# design.net
KiCad netlist of a schematic drawn in EasyEDA Pro
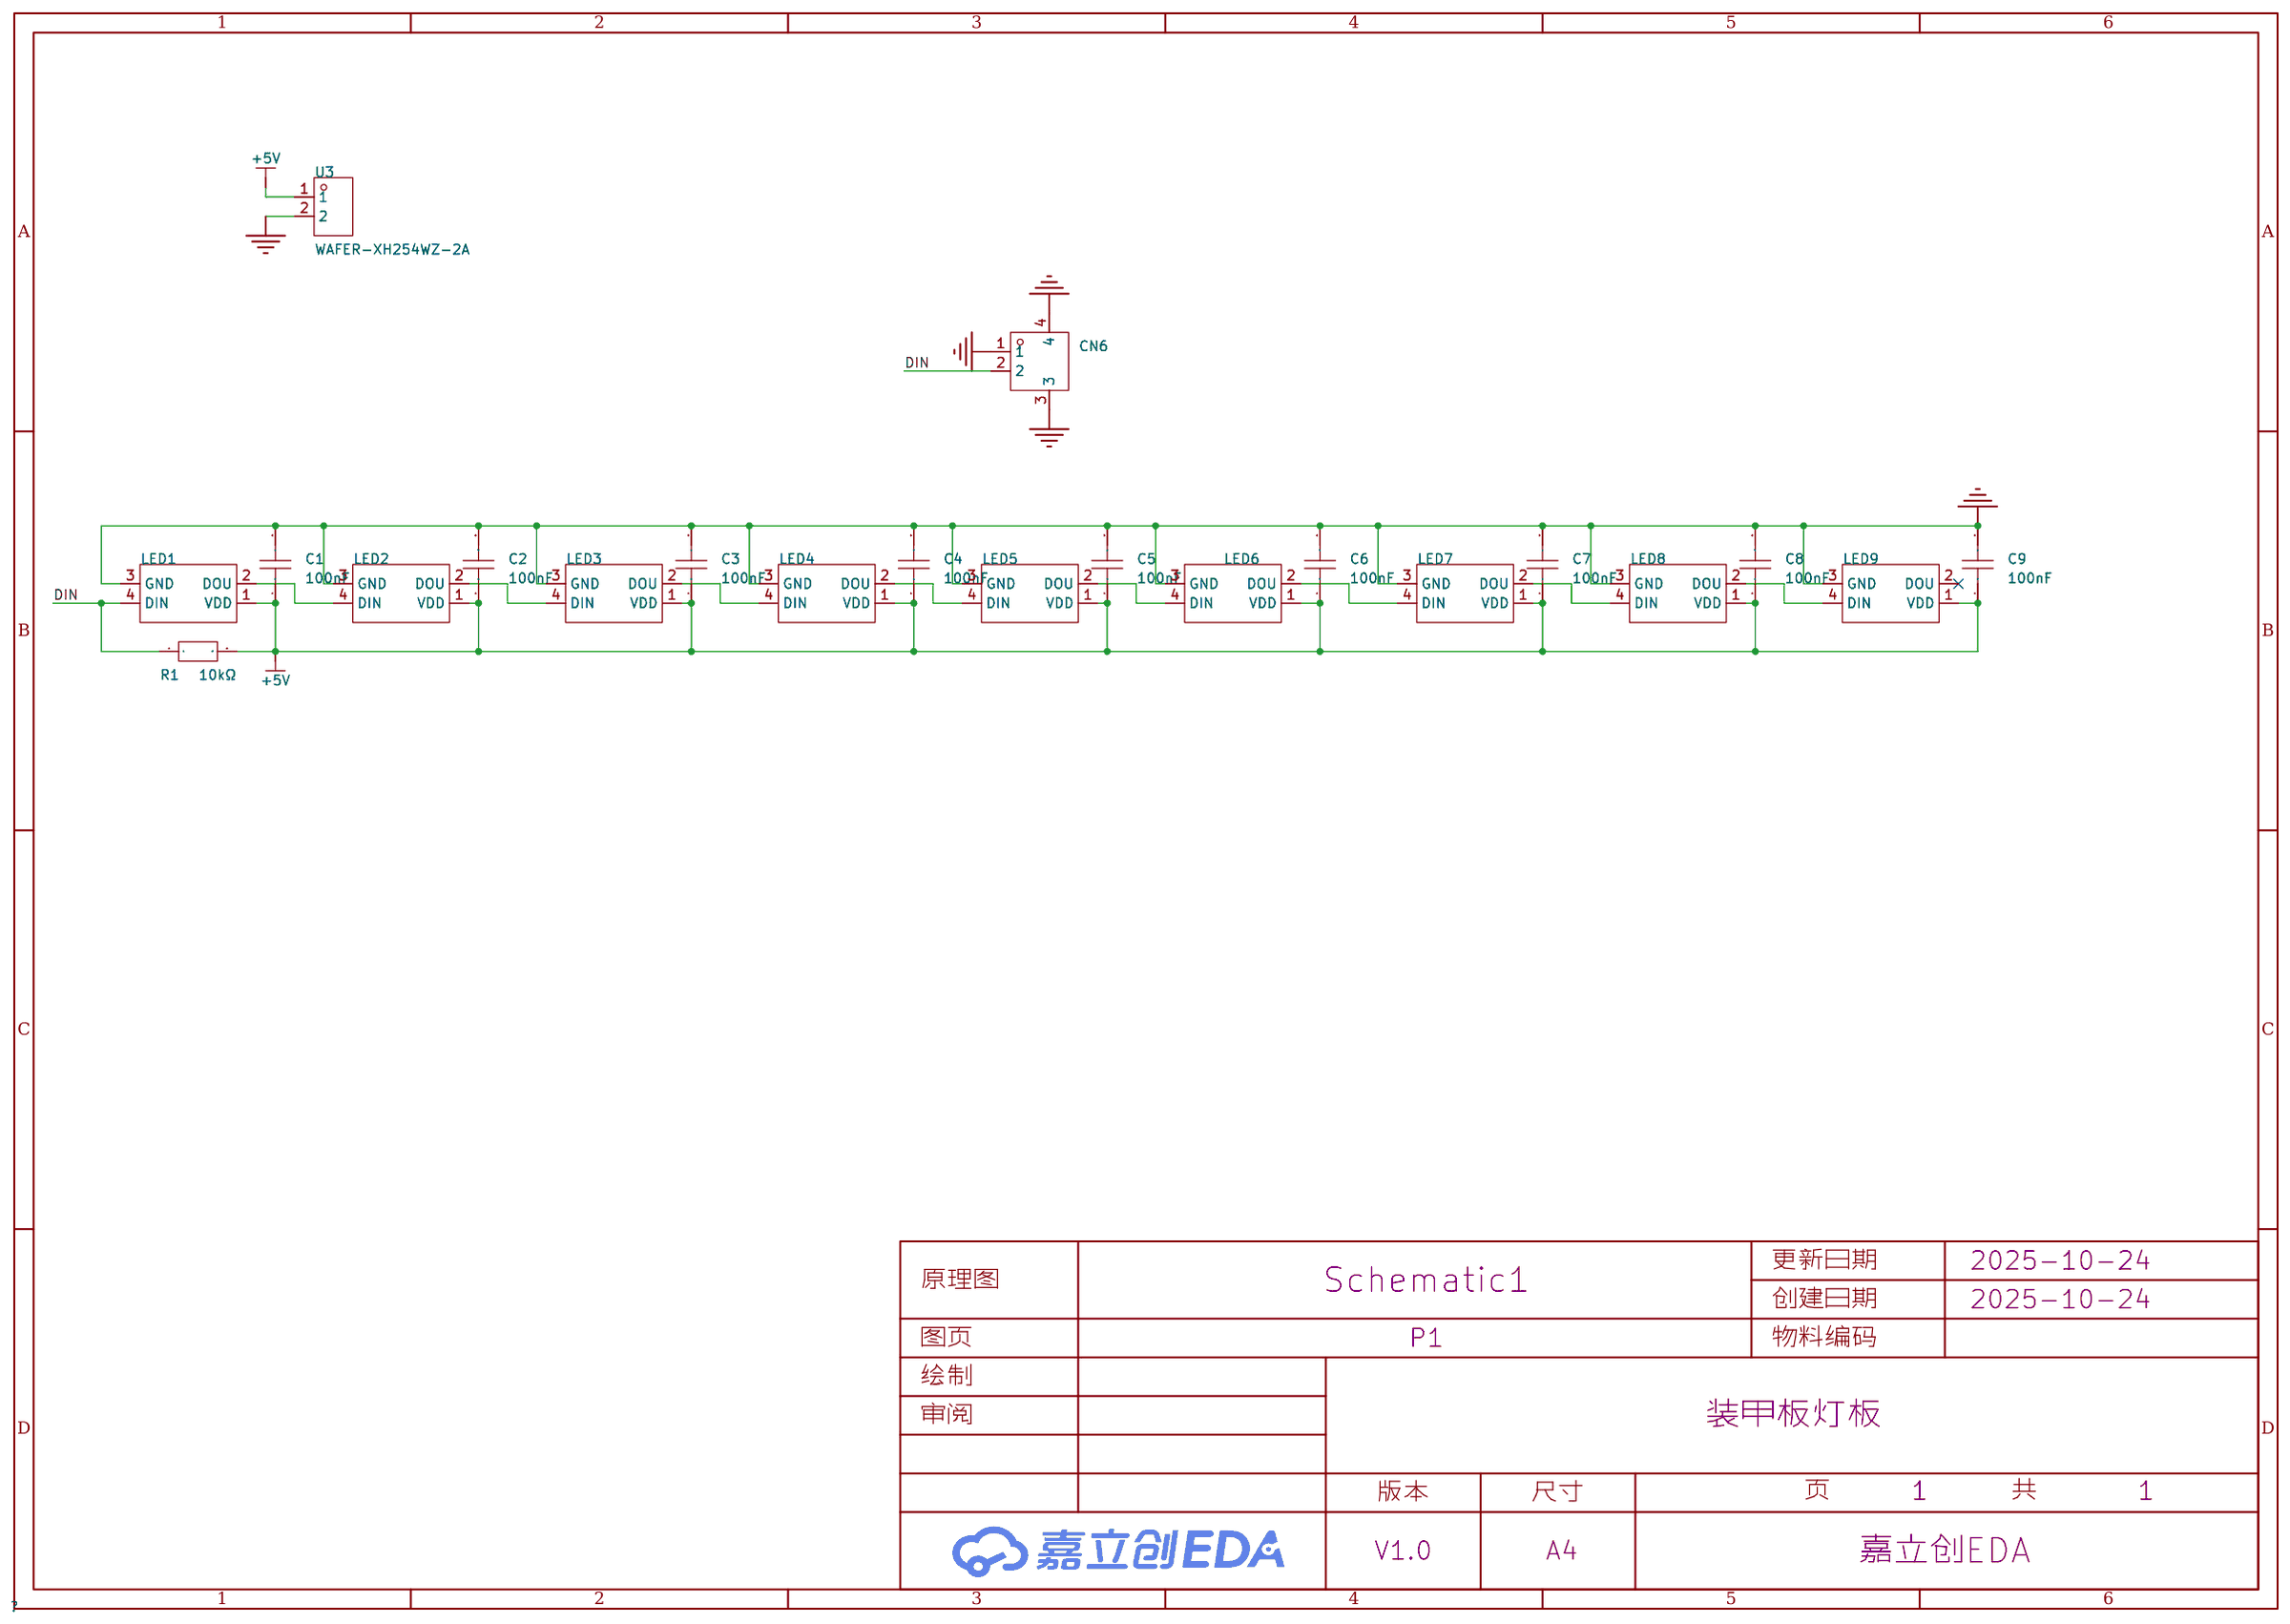
[diagram p0: schematic sheet]

(export (version "E")
  (design (tool "Eeschema 10.0.6"))
  (components
    (comp (ref "C1")
      (value "100nF")
      (footprint "easyedapro:C0603")
      (description "容值:100nF;精度:±20%;额定电压:50V;")
      (fields
        (field (name "Manufacturer Part") "NL0603B104M500CPBN")
        (field (name "Manufacturer") "HUI JU(汇聚)")
      )
      (libsource (lib "easyedapro") (part "NL0603B104M500CPBN"))
    )
    (comp (ref "C2")
      (value "100nF")
      (footprint "easyedapro:C0603")
      (description "容值:100nF;精度:±20%;额定电压:50V;")
      (fields
        (field (name "Manufacturer Part") "NL0603B104M500CPBN")
        (field (name "Manufacturer") "HUI JU(汇聚)")
      )
      (libsource (lib "easyedapro") (part "NL0603B104M500CPBN"))
    )
    (comp (ref "C3")
      (value "100nF")
      (footprint "easyedapro:C0603")
      (description "容值:100nF;精度:±20%;额定电压:50V;")
      (fields
        (field (name "Manufacturer Part") "NL0603B104M500CPBN")
        (field (name "Manufacturer") "HUI JU(汇聚)")
      )
      (libsource (lib "easyedapro") (part "NL0603B104M500CPBN"))
    )
    (comp (ref "C4")
      (value "100nF")
      (footprint "easyedapro:C0603")
      (description "容值:100nF;精度:±20%;额定电压:50V;")
      (fields
        (field (name "Manufacturer Part") "NL0603B104M500CPBN")
        (field (name "Manufacturer") "HUI JU(汇聚)")
      )
      (libsource (lib "easyedapro") (part "NL0603B104M500CPBN"))
    )
    (comp (ref "C5")
      (value "100nF")
      (footprint "easyedapro:C0603")
      (description "容值:100nF;精度:±20%;额定电压:50V;")
      (fields
        (field (name "Manufacturer Part") "NL0603B104M500CPBN")
        (field (name "Manufacturer") "HUI JU(汇聚)")
      )
      (libsource (lib "easyedapro") (part "NL0603B104M500CPBN"))
    )
    (comp (ref "C6")
      (value "100nF")
      (footprint "easyedapro:C0603")
      (description "容值:100nF;精度:±20%;额定电压:50V;")
      (fields
        (field (name "Manufacturer Part") "NL0603B104M500CPBN")
        (field (name "Manufacturer") "HUI JU(汇聚)")
      )
      (libsource (lib "easyedapro") (part "NL0603B104M500CPBN"))
    )
    (comp (ref "C7")
      (value "100nF")
      (footprint "easyedapro:C0603")
      (description "容值:100nF;精度:±20%;额定电压:50V;")
      (fields
        (field (name "Manufacturer Part") "NL0603B104M500CPBN")
        (field (name "Manufacturer") "HUI JU(汇聚)")
      )
      (libsource (lib "easyedapro") (part "NL0603B104M500CPBN"))
    )
    (comp (ref "C8")
      (value "100nF")
      (footprint "easyedapro:C0603")
      (description "容值:100nF;精度:±20%;额定电压:50V;")
      (fields
        (field (name "Manufacturer Part") "NL0603B104M500CPBN")
        (field (name "Manufacturer") "HUI JU(汇聚)")
      )
      (libsource (lib "easyedapro") (part "NL0603B104M500CPBN"))
    )
    (comp (ref "C9")
      (value "100nF")
      (footprint "easyedapro:C0603")
      (description "容值:100nF;精度:±20%;额定电压:50V;")
      (fields
        (field (name "Manufacturer Part") "NL0603B104M500CPBN")
        (field (name "Manufacturer") "HUI JU(汇聚)")
      )
      (libsource (lib "easyedapro") (part "NL0603B104M500CPBN"))
    )
    (comp (ref "CN6")
      (value "X1251WVS-02HF-LPSW")
      (footprint "easyedapro:郭哥CAN2脚母接口")
      (fields (field (name "Manufacturer") "XKB Enterprise"))
      (libsource (lib "easyedapro") (part "X1251WVS-02HF-LPSW"))
    )
    (comp (ref "LED1")
      (value "XL-5050RGBC-2812B")
      (footprint "easyedapro:LED-SMD_4P-L5.0-W5.0-BL_XL-5050RGBC")
      (description "5050幻彩透明  内置驱动  IC WS2812B")
      (fields (field (name "Manufacturer") "XINGLIGHT(成兴光)"))
      (libsource (lib "easyedapro") (part "XL-5050RGBC-WS2812B"))
    )
    (comp (ref "LED2")
      (value "XL-5050RGBC-2812B")
      (footprint "easyedapro:LED-SMD_4P-L5.0-W5.0-BL_XL-5050RGBC")
      (description "5050幻彩透明  内置驱动  IC WS2812B")
      (fields (field (name "Manufacturer") "XINGLIGHT(成兴光)"))
      (libsource (lib "easyedapro") (part "XL-5050RGBC-WS2812B"))
    )
    (comp (ref "LED3")
      (value "XL-5050RGBC-2812B")
      (footprint "easyedapro:LED-SMD_4P-L5.0-W5.0-BL_XL-5050RGBC")
      (description "5050幻彩透明  内置驱动  IC WS2812B")
      (fields (field (name "Manufacturer") "XINGLIGHT(成兴光)"))
      (libsource (lib "easyedapro") (part "XL-5050RGBC-WS2812B"))
    )
    (comp (ref "LED4")
      (value "XL-5050RGBC-2812B")
      (footprint "easyedapro:LED-SMD_4P-L5.0-W5.0-BL_XL-5050RGBC")
      (description "5050幻彩透明  内置驱动  IC WS2812B")
      (fields (field (name "Manufacturer") "XINGLIGHT(成兴光)"))
      (libsource (lib "easyedapro") (part "XL-5050RGBC-WS2812B"))
    )
    (comp (ref "LED5")
      (value "XL-5050RGBC-2812B")
      (footprint "easyedapro:LED-SMD_4P-L5.0-W5.0-BL_XL-5050RGBC")
      (description "5050幻彩透明  内置驱动  IC WS2812B")
      (fields (field (name "Manufacturer") "XINGLIGHT(成兴光)"))
      (libsource (lib "easyedapro") (part "XL-5050RGBC-WS2812B"))
    )
    (comp (ref "LED6")
      (value "XL-5050RGBC-2812B")
      (footprint "easyedapro:LED-SMD_4P-L5.0-W5.0-BL_XL-5050RGBC")
      (description "5050幻彩透明  内置驱动  IC WS2812B")
      (fields (field (name "Manufacturer") "XINGLIGHT(成兴光)"))
      (libsource (lib "easyedapro") (part "XL-5050RGBC-WS2812B"))
    )
    (comp (ref "LED7")
      (value "XL-5050RGBC-2812B")
      (footprint "easyedapro:LED-SMD_4P-L5.0-W5.0-BL_XL-5050RGBC")
      (description "5050幻彩透明  内置驱动  IC WS2812B")
      (fields (field (name "Manufacturer") "XINGLIGHT(成兴光)"))
      (libsource (lib "easyedapro") (part "XL-5050RGBC-WS2812B"))
    )
    (comp (ref "LED8")
      (value "XL-5050RGBC-2812B")
      (footprint "easyedapro:LED-SMD_4P-L5.0-W5.0-BL_XL-5050RGBC")
      (description "5050幻彩透明  内置驱动  IC WS2812B")
      (fields (field (name "Manufacturer") "XINGLIGHT(成兴光)"))
      (libsource (lib "easyedapro") (part "XL-5050RGBC-WS2812B"))
    )
    (comp (ref "LED9")
      (value "XL-5050RGBC-2812B")
      (footprint "easyedapro:LED-SMD_4P-L5.0-W5.0-BL_XL-5050RGBC")
      (description "5050幻彩透明  内置驱动  IC WS2812B")
      (fields (field (name "Manufacturer") "XINGLIGHT(成兴光)"))
      (libsource (lib "easyedapro") (part "XL-5050RGBC-WS2812B"))
    )
    (comp (ref "R1")
      (value "10kΩ")
      (footprint "easyedapro:R0603")
      (description "电阻类型:薄膜电阻;阻值:10kΩ;精度:±0.1%;功率:100mW;工作电压:75V;温度系数:±50ppm/°C;")
      (fields
        (field (name "Manufacturer Part") "TC0350B1002T5F")
        (field (name "Manufacturer") "UNI-ROYAL(厚声)")
      )
      (libsource (lib "easyedapro") (part "TC0350B1002T5F"))
    )
    (comp (ref "U3")
      (value "WAFER-XH254WZ-2A")
      (footprint "easyedapro:CONN-TH_2P-P2.50_WAFER-XH254WZ-2A")
      (description "插针结构:1x2P;间距:2.54mm;安装方式:弯插;参考系列:XH;总PIN数:2P;排数:1;每排PIN数:2;额定电流:3A;触头材质:黄铜;工作温度:-25°C~+85°C;")
      (fields (field (name "Manufacturer") "HANBO(汉博)"))
      (libsource (lib "easyedapro") (part "WAFER-XH254WZ-2A"))
    )
  )
  (nets
    (net (code "1") (name "+5V") (class "Default")
      (node (ref "C1") (pin "1") (pinfunction "1_1") (pintype "unspecified"))
      (node (ref "C2") (pin "1") (pinfunction "1_1") (pintype "unspecified"))
      (node (ref "C3") (pin "1") (pinfunction "1_1") (pintype "unspecified"))
      (node (ref "C4") (pin "1") (pinfunction "1_1") (pintype "unspecified"))
      (node (ref "C5") (pin "1") (pinfunction "1_1") (pintype "unspecified"))
      (node (ref "C6") (pin "1") (pinfunction "1_1") (pintype "unspecified"))
      (node (ref "C7") (pin "1") (pinfunction "1_1") (pintype "unspecified"))
      (node (ref "C8") (pin "1") (pinfunction "1_1") (pintype "unspecified"))
      (node (ref "C9") (pin "1") (pinfunction "1_1") (pintype "unspecified"))
      (node (ref "LED1") (pin "1") (pinfunction "VDD_1") (pintype "unspecified"))
      (node (ref "LED2") (pin "1") (pinfunction "VDD_1") (pintype "unspecified"))
      (node (ref "LED3") (pin "1") (pinfunction "VDD_1") (pintype "unspecified"))
      (node (ref "LED4") (pin "1") (pinfunction "VDD_1") (pintype "unspecified"))
      (node (ref "LED5") (pin "1") (pinfunction "VDD_1") (pintype "unspecified"))
      (node (ref "LED6") (pin "1") (pinfunction "VDD_1") (pintype "unspecified"))
      (node (ref "LED7") (pin "1") (pinfunction "VDD_1") (pintype "unspecified"))
      (node (ref "LED8") (pin "1") (pinfunction "VDD_1") (pintype "unspecified"))
      (node (ref "LED9") (pin "1") (pinfunction "VDD_1") (pintype "unspecified"))
      (node (ref "R1") (pin "2") (pinfunction "2_2") (pintype "unspecified"))
      (node (ref "U3") (pin "1") (pinfunction "1_1") (pintype "unspecified"))
    )
    (net (code "2") (name "/DIN") (class "Default")
      (node (ref "CN6") (pin "2") (pinfunction "2_2") (pintype "unspecified"))
      (node (ref "LED1") (pin "4") (pinfunction "DIN_4") (pintype "unspecified"))
      (node (ref "R1") (pin "1") (pinfunction "1_1") (pintype "unspecified"))
    )
    (net (code "3") (name "GND") (class "Default")
      (node (ref "C1") (pin "2") (pinfunction "2_2") (pintype "unspecified"))
      (node (ref "C2") (pin "2") (pinfunction "2_2") (pintype "unspecified"))
      (node (ref "C3") (pin "2") (pinfunction "2_2") (pintype "unspecified"))
      (node (ref "C4") (pin "2") (pinfunction "2_2") (pintype "unspecified"))
      (node (ref "C5") (pin "2") (pinfunction "2_2") (pintype "unspecified"))
      (node (ref "C6") (pin "2") (pinfunction "2_2") (pintype "unspecified"))
      (node (ref "C7") (pin "2") (pinfunction "2_2") (pintype "unspecified"))
      (node (ref "C8") (pin "2") (pinfunction "2_2") (pintype "unspecified"))
      (node (ref "C9") (pin "2") (pinfunction "2_2") (pintype "unspecified"))
      (node (ref "CN6") (pin "1") (pinfunction "1_1") (pintype "unspecified"))
      (node (ref "CN6") (pin "3") (pinfunction "3_3") (pintype "unspecified"))
      (node (ref "CN6") (pin "4") (pinfunction "4_4") (pintype "unspecified"))
      (node (ref "LED1") (pin "3") (pinfunction "GND_3") (pintype "unspecified"))
      (node (ref "LED2") (pin "3") (pinfunction "GND_3") (pintype "unspecified"))
      (node (ref "LED3") (pin "3") (pinfunction "GND_3") (pintype "unspecified"))
      (node (ref "LED4") (pin "3") (pinfunction "GND_3") (pintype "unspecified"))
      (node (ref "LED5") (pin "3") (pinfunction "GND_3") (pintype "unspecified"))
      (node (ref "LED6") (pin "3") (pinfunction "GND_3") (pintype "unspecified"))
      (node (ref "LED7") (pin "3") (pinfunction "GND_3") (pintype "unspecified"))
      (node (ref "LED8") (pin "3") (pinfunction "GND_3") (pintype "unspecified"))
      (node (ref "LED9") (pin "3") (pinfunction "GND_3") (pintype "unspecified"))
      (node (ref "U3") (pin "2") (pinfunction "2_2") (pintype "unspecified"))
    )
    (net (code "4") (name "Net-(LED1-DOU)") (class "Default")
      (node (ref "LED1") (pin "2") (pinfunction "DOU_2") (pintype "unspecified"))
      (node (ref "LED2") (pin "4") (pinfunction "DIN_4") (pintype "unspecified"))
    )
    (net (code "5") (name "Net-(LED2-DOU)") (class "Default")
      (node (ref "LED2") (pin "2") (pinfunction "DOU_2") (pintype "unspecified"))
      (node (ref "LED3") (pin "4") (pinfunction "DIN_4") (pintype "unspecified"))
    )
    (net (code "6") (name "Net-(LED3-DOU)") (class "Default")
      (node (ref "LED3") (pin "2") (pinfunction "DOU_2") (pintype "unspecified"))
      (node (ref "LED4") (pin "4") (pinfunction "DIN_4") (pintype "unspecified"))
    )
    (net (code "7") (name "Net-(LED4-DOU)") (class "Default")
      (node (ref "LED4") (pin "2") (pinfunction "DOU_2") (pintype "unspecified"))
      (node (ref "LED5") (pin "4") (pinfunction "DIN_4") (pintype "unspecified"))
    )
    (net (code "8") (name "Net-(LED5-DOU)") (class "Default")
      (node (ref "LED5") (pin "2") (pinfunction "DOU_2") (pintype "unspecified"))
      (node (ref "LED6") (pin "4") (pinfunction "DIN_4") (pintype "unspecified"))
    )
    (net (code "9") (name "Net-(LED6-DOU)") (class "Default")
      (node (ref "LED6") (pin "2") (pinfunction "DOU_2") (pintype "unspecified"))
      (node (ref "LED7") (pin "4") (pinfunction "DIN_4") (pintype "unspecified"))
    )
    (net (code "10") (name "Net-(LED7-DOU)") (class "Default")
      (node (ref "LED7") (pin "2") (pinfunction "DOU_2") (pintype "unspecified"))
      (node (ref "LED8") (pin "4") (pinfunction "DIN_4") (pintype "unspecified"))
    )
    (net (code "11") (name "Net-(LED8-DOU)") (class "Default")
      (node (ref "LED8") (pin "2") (pinfunction "DOU_2") (pintype "unspecified"))
      (node (ref "LED9") (pin "4") (pinfunction "DIN_4") (pintype "unspecified"))
    )
    (net (code "12") (name "unconnected-(LED9-DOU-Pad2)") (class "Default")
      (node (ref "LED9") (pin "2") (pinfunction "DOU_2") (pintype "unspecified+no_connect"))
    )
  )
)
